# can_unisolated_lemo.net
KiCad netlist of a schematic drawn in Altium Designer
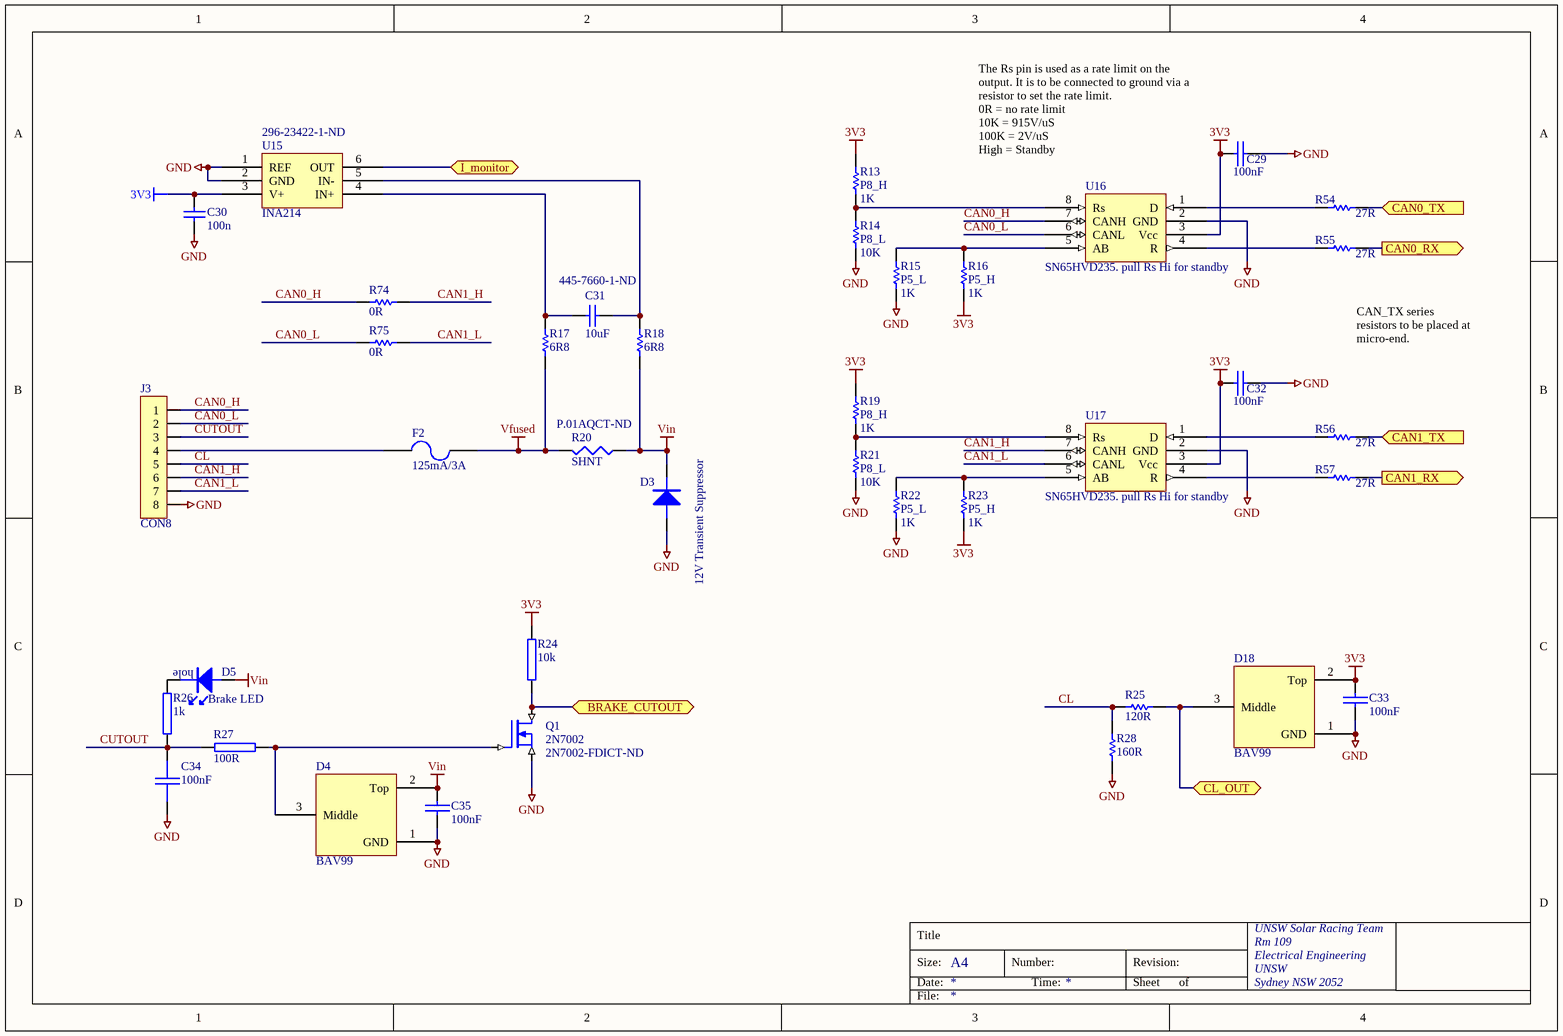
[diagram p0: can_unisolated_lemo.SchDoc]

(export (version "E")
  (design (tool "Eeschema 10.0.6"))
  (components
    (comp (ref "C29")
      (value "100nF")
      (footprint "0603")
      (description "Capacitor")
      (libsource (lib "*") (part "CAP"))
    )
    (comp (ref "C30")
      (value "100n")
      (footprint "0603")
      (description "Capacitor (Semiconductor SIM Model)")
      (fields (field (name "PUBLISHER") "Altium Limited"))
      (libsource (lib "Miscellaneous Devices") (part "Cap Semi"))
    )
    (comp (ref "C31")
      (value "10uF")
      (footprint "0805")
      (description "Capacitor (Semiconductor SIM Model)")
      (fields
        (field (name "SUPPLIER PART NUMBER 1") "445-7660-1-ND")
        (field (name "MANUFACTURER") "TDK Corporation")
        (field (name "MANUFACTURER PART NUMBER") "C2012X5R1A106K125AB")
      )
      (libsource (lib "Miscellaneous Devices") (part "Cap Semi"))
    )
    (comp (ref "C32")
      (value "100nF")
      (footprint "0603")
      (description "Capacitor")
      (libsource (lib "*") (part "CAP"))
    )
    (comp (ref "C33")
      (value "100nF")
      (footprint "0603")
      (description "Capacitor")
      (libsource (lib "*") (part "CAP"))
    )
    (comp (ref "C34")
      (value "100nF")
      (footprint "0603")
      (description "Capacitor")
      (libsource (lib "Miscellaneous Devices") (part "CAP"))
    )
    (comp (ref "C35")
      (value "100nF")
      (footprint "0603")
      (description "Capacitor")
      (libsource (lib "*") (part "CAP"))
    )
    (comp (ref "D3")
      (value "12V Transient Suppressor")
      (footprint "SMA")
      (description "Diode")
      (libsource (lib "RCLDQ") (part "DIODE"))
    )
    (comp (ref "D4")
      (value "BAV99")
      (footprint "SOT23-3")
      (description "Dual Diode")
      (libsource (lib "Miscellaneous") (part "BAV99"))
    )
    (comp (ref "D5")
      (value "Brake LED")
      (footprint "LED0.1")
      (description "through hole LED")
      (libsource (lib "RCLDQ") (part "LED_HOLE"))
    )
    (comp (ref "D18")
      (value "BAV99")
      (footprint "SOT23-3")
      (description "Dual Diode")
      (libsource (lib "Miscellaneous") (part "BAV99"))
    )
    (comp (ref "F2")
      (value "125mA/3A")
      (footprint "LITTELFUSE-154")
      (description "Fuse")
      (libsource (lib "*") (part "FUSE2"))
    )
    (comp (ref "J3")
      (value "CON8")
      (footprint "LEMO_1B_308")
      (description "Connector")
      (libsource (lib "steve") (part "CON8"))
    )
    (comp (ref "Q1")
      (value "2N7002")
      (footprint "SOT23-3")
      (description "MOSFET N-CH 60V 115MA SOT23-3")
      (fields
        (field (name "SUPPLIER PART NUMBER 1") "2N7002-FDICT-ND")
        (field (name "MANUFACTURER") "Diodes Inc")
        (field (name "MANUFACTURER PART NUMBER") "2N7002-7-F")
      )
      (libsource (lib "*") (part "N-MOSFET"))
    )
    (comp (ref "R13")
      (value "P8_H")
      (footprint "0603")
      (description "Semiconductor Resistor")
      (fields (field (name "ALTIUM_VALUE") "1K") (field (name "PUBLISHER") "Altium Limited"))
      (libsource (lib "Miscellaneous Devices") (part "Res Semi"))
    )
    (comp (ref "R14")
      (value "P8_L")
      (footprint "0603")
      (description "Semiconductor Resistor")
      (fields (field (name "ALTIUM_VALUE") "10K") (field (name "PUBLISHER") "Altium Limited"))
      (libsource (lib "Miscellaneous Devices") (part "Res Semi"))
    )
    (comp (ref "R15")
      (value "P5_L")
      (footprint "0603")
      (description "Semiconductor Resistor")
      (fields (field (name "ALTIUM_VALUE") "1K") (field (name "PUBLISHER") "Altium Limited"))
      (libsource (lib "Miscellaneous Devices") (part "Res Semi"))
    )
    (comp (ref "R16")
      (value "P5_H")
      (footprint "0603")
      (description "Semiconductor Resistor")
      (fields (field (name "ALTIUM_VALUE") "1K") (field (name "PUBLISHER") "Altium Limited"))
      (libsource (lib "Miscellaneous Devices") (part "Res Semi"))
    )
    (comp (ref "R17")
      (value "6R8")
      (footprint "0603")
      (description "Semiconductor Resistor")
      (fields
        (field (name "MANUFACTURER") "Panasonic Electronic Components")
        (field (name "MANUFACTURER PART NUMBER") "ERJ-3GEYJ6R8V")
        (field (name "PUBLISHER") "Altium Limited")
      )
      (libsource (lib "Miscellaneous Devices") (part "Res Semi"))
    )
    (comp (ref "R18")
      (value "6R8")
      (footprint "0603")
      (description "Semiconductor Resistor")
      (fields
        (field (name "MANUFACTURER") "Panasonic Electronic Components")
        (field (name "MANUFACTURER PART NUMBER") "ERJ-3GEYJ6R8V")
        (field (name "PUBLISHER") "Altium Limited")
      )
      (libsource (lib "Miscellaneous Devices") (part "Res Semi"))
    )
    (comp (ref "R19")
      (value "P8_H")
      (footprint "0603")
      (description "Semiconductor Resistor")
      (fields (field (name "ALTIUM_VALUE") "1K") (field (name "PUBLISHER") "Altium Limited"))
      (libsource (lib "Miscellaneous Devices") (part "Res Semi"))
    )
    (comp (ref "R20")
      (value "SHNT")
      (footprint "0805")
      (description "Resistor")
      (fields
        (field (name "SUPPLIER PART NUMBER 1") "P.01AQCT-ND")
        (field (name "MANUFACTURER") "Panasonic Electronic Components")
        (field (name "MANUFACTURER PART NUMBER") "ERJ-6BWFR010V")
        (field (name "PUBLISHER") "Altium Limited")
      )
      (libsource (lib "Miscellaneous Devices") (part "Res3"))
    )
    (comp (ref "R21")
      (value "P8_L")
      (footprint "0603")
      (description "Semiconductor Resistor")
      (fields (field (name "ALTIUM_VALUE") "10K") (field (name "PUBLISHER") "Altium Limited"))
      (libsource (lib "Miscellaneous Devices") (part "Res Semi"))
    )
    (comp (ref "R22")
      (value "P5_L")
      (footprint "0603")
      (description "Semiconductor Resistor")
      (fields (field (name "ALTIUM_VALUE") "1K") (field (name "PUBLISHER") "Altium Limited"))
      (libsource (lib "Miscellaneous Devices") (part "Res Semi"))
    )
    (comp (ref "R23")
      (value "P5_H")
      (footprint "0603")
      (description "Semiconductor Resistor")
      (fields (field (name "ALTIUM_VALUE") "1K") (field (name "PUBLISHER") "Altium Limited"))
      (libsource (lib "Miscellaneous Devices") (part "Res Semi"))
    )
    (comp (ref "R24")
      (value "10k")
      (footprint "0603")
      (description "Standard Resistor")
      (libsource (lib "*") (part "RES"))
    )
    (comp (ref "R25")
      (value "120R")
      (footprint "0603")
      (description "Semiconductor Resistor")
      (fields
        (field (name "MANUFACTURER") "Panasonic Electronic Components")
        (field (name "MANUFACTURER PART NUMBER") "ERJ-3EKF1200V")
        (field (name "PUBLISHER") "Altium Limited")
      )
      (libsource (lib "Miscellaneous Devices") (part "Res Semi"))
    )
    (comp (ref "R26")
      (value "1k")
      (footprint "0603")
      (description "Standard Resistor")
      (libsource (lib "*") (part "RES"))
    )
    (comp (ref "R27")
      (value "100R")
      (footprint "0603")
      (description "Standard Resistor")
      (libsource (lib "*") (part "RES"))
    )
    (comp (ref "R28")
      (value "160R")
      (footprint "0603")
      (description "Semiconductor Resistor")
      (fields
        (field (name "MANUFACTURER") "Panasonic Electronic Components")
        (field (name "MANUFACTURER PART NUMBER") "ERJ-2RKF1600X")
        (field (name "PUBLISHER") "Altium Limited")
      )
      (libsource (lib "Miscellaneous Devices") (part "Res Semi"))
    )
    (comp (ref "R54")
      (value "27R")
      (footprint "0603")
      (description "Semiconductor Resistor")
      (fields
        (field (name "MANUFACTURER") "Panasonic Electronic Components")
        (field (name "MANUFACTURER PART NUMBER") "ERJ-3EKF27R0V")
        (field (name "PUBLISHER") "Altium Limited")
      )
      (libsource (lib "Miscellaneous Devices") (part "Res Semi"))
    )
    (comp (ref "R55")
      (value "27R")
      (footprint "0603")
      (description "Semiconductor Resistor")
      (fields
        (field (name "MANUFACTURER") "Panasonic Electronic Components")
        (field (name "MANUFACTURER PART NUMBER") "ERJ-3EKF27R0V")
        (field (name "PUBLISHER") "Altium Limited")
      )
      (libsource (lib "Miscellaneous Devices") (part "Res Semi"))
    )
    (comp (ref "R56")
      (value "27R")
      (footprint "0603")
      (description "Semiconductor Resistor")
      (fields
        (field (name "MANUFACTURER") "Panasonic Electronic Components")
        (field (name "MANUFACTURER PART NUMBER") "ERJ-3EKF27R0V")
        (field (name "PUBLISHER") "Altium Limited")
      )
      (libsource (lib "Miscellaneous Devices") (part "Res Semi"))
    )
    (comp (ref "R57")
      (value "27R")
      (footprint "0603")
      (description "Semiconductor Resistor")
      (fields
        (field (name "MANUFACTURER") "Panasonic Electronic Components")
        (field (name "MANUFACTURER PART NUMBER") "ERJ-3EKF27R0V")
        (field (name "PUBLISHER") "Altium Limited")
      )
      (libsource (lib "Miscellaneous Devices") (part "Res Semi"))
    )
    (comp (ref "R74")
      (value "0R")
      (footprint "0603")
      (description "Semiconductor Resistor")
      (fields (field (name "PUBLISHER") "Altium Limited"))
      (libsource (lib "Miscellaneous Devices") (part "Res Semi"))
    )
    (comp (ref "R75")
      (value "0R")
      (footprint "0603")
      (description "Semiconductor Resistor")
      (fields (field (name "PUBLISHER") "Altium Limited"))
      (libsource (lib "Miscellaneous Devices") (part "Res Semi"))
    )
    (comp (ref "U15")
      (value "INA214")
      (footprint "SC70-6")
      (description "Current Shunt Monitor")
      (fields
        (field (name "SUPPLIER PART NUMBER 1") "296-23422-1-ND")
        (field (name "MANUFACTURER") "Texas Instruments")
        (field (name "MANUFACTURER PART NUMBER") "INA214AIDCKT")
      )
      (libsource (lib "MiscellaneousIC") (part "ina214"))
    )
    (comp (ref "U16")
      (value "SN65HVD235. pull Rs Hi for standby")
      (footprint "SO8")
      (description "3.3V CAN XCVR W/STANDBY")
      (libsource (lib "CAN") (part "SN65HVD235"))
    )
    (comp (ref "U17")
      (value "SN65HVD235. pull Rs Hi for standby")
      (footprint "SO8")
      (description "3.3V CAN XCVR W/STANDBY")
      (libsource (lib "CAN") (part "SN65HVD235"))
    )
  )
  (nets
    (net (code "1") (name "/BRAKE_CUTOUT") (class "Default")
      (node (ref "Q1") (pin "D") (pinfunction "D_D") (pintype "input"))
      (node (ref "R24") (pin "1") (pintype "passive"))
    )
    (net (code "2") (name "/CAN0_H") (class "Default")
      (node (ref "J3") (pin "1") (pinfunction "1_1") (pintype "passive"))
      (node (ref "R74") (pin "1") (pinfunction "1_1") (pintype "passive"))
      (node (ref "U16") (pin "7") (pinfunction "CANH_7") (pintype "bidirectional"))
    )
    (net (code "3") (name "/CAN0_L") (class "Default")
      (node (ref "J3") (pin "2") (pinfunction "2_2") (pintype "passive"))
      (node (ref "R75") (pin "1") (pinfunction "1_1") (pintype "passive"))
      (node (ref "U16") (pin "6") (pinfunction "CANL_6") (pintype "bidirectional"))
    )
    (net (code "4") (name "/CAN0_RX") (class "Default")
      (node (ref "R55") (pin "1") (pinfunction "1_1") (pintype "passive"))
    )
    (net (code "5") (name "/CAN0_TX") (class "Default")
      (node (ref "R54") (pin "1") (pinfunction "1_1") (pintype "passive"))
    )
    (net (code "6") (name "/CAN1_H") (class "Default")
      (node (ref "J3") (pin "6") (pinfunction "6_6") (pintype "passive"))
      (node (ref "R74") (pin "2") (pinfunction "2_2") (pintype "passive"))
      (node (ref "U17") (pin "7") (pinfunction "CANH_7") (pintype "bidirectional"))
    )
    (net (code "7") (name "/CAN1_L") (class "Default")
      (node (ref "J3") (pin "7") (pinfunction "7_7") (pintype "passive"))
      (node (ref "R75") (pin "2") (pinfunction "2_2") (pintype "passive"))
      (node (ref "U17") (pin "6") (pinfunction "CANL_6") (pintype "bidirectional"))
    )
    (net (code "8") (name "/CAN1_RX") (class "Default")
      (node (ref "R57") (pin "1") (pinfunction "1_1") (pintype "passive"))
    )
    (net (code "9") (name "/CAN1_TX") (class "Default")
      (node (ref "R56") (pin "1") (pinfunction "1_1") (pintype "passive"))
    )
    (net (code "10") (name "/CL") (class "Default")
      (node (ref "J3") (pin "5") (pinfunction "5_5") (pintype "passive"))
      (node (ref "R25") (pin "2") (pinfunction "2_2") (pintype "passive"))
      (node (ref "R28") (pin "2") (pinfunction "2_2") (pintype "passive"))
    )
    (net (code "11") (name "/CL_OUT") (class "Default")
      (node (ref "D18") (pin "3") (pinfunction "Middle_3") (pintype "passive"))
      (node (ref "R25") (pin "1") (pinfunction "1_1") (pintype "passive"))
    )
    (net (code "12") (name "/CUTOUT") (class "Default")
      (node (ref "C34") (pin "1") (pinfunction "1_1") (pintype "passive"))
      (node (ref "J3") (pin "3") (pinfunction "3_3") (pintype "passive"))
      (node (ref "R26") (pin "2") (pintype "passive"))
      (node (ref "R27") (pin "1") (pintype "passive"))
    )
    (net (code "13") (name "/I_monitor") (class "Default")
      (node (ref "U15") (pin "6") (pinfunction "OUT_6") (pintype "power_in"))
    )
    (net (code "14") (name "3V3") (class "Default")
      (node (ref "C29") (pin "2") (pinfunction "2_2") (pintype "passive"))
      (node (ref "C30") (pin "2") (pinfunction "2_2") (pintype "passive"))
      (node (ref "C32") (pin "2") (pinfunction "2_2") (pintype "passive"))
      (node (ref "C33") (pin "1") (pinfunction "1_1") (pintype "passive"))
      (node (ref "D18") (pin "2") (pinfunction "Top_2") (pintype "passive"))
      (node (ref "R13") (pin "2") (pinfunction "2_2") (pintype "passive"))
      (node (ref "R16") (pin "1") (pinfunction "1_1") (pintype "passive"))
      (node (ref "R19") (pin "2") (pinfunction "2_2") (pintype "passive"))
      (node (ref "R23") (pin "1") (pinfunction "1_1") (pintype "passive"))
      (node (ref "R24") (pin "2") (pintype "passive"))
      (node (ref "U15") (pin "3") (pinfunction "V+_3") (pintype "power_in"))
      (node (ref "U16") (pin "3") (pinfunction "Vcc_3") (pintype "power_in"))
      (node (ref "U17") (pin "3") (pinfunction "Vcc_3") (pintype "power_in"))
    )
    (net (code "15") (name "GND") (class "Default")
      (node (ref "C29") (pin "1") (pinfunction "1_1") (pintype "passive"))
      (node (ref "C30") (pin "1") (pinfunction "1_1") (pintype "passive"))
      (node (ref "C32") (pin "1") (pinfunction "1_1") (pintype "passive"))
      (node (ref "C33") (pin "2") (pinfunction "2_2") (pintype "passive"))
      (node (ref "C34") (pin "2") (pinfunction "2_2") (pintype "passive"))
      (node (ref "C35") (pin "2") (pinfunction "2_2") (pintype "passive"))
      (node (ref "D18") (pin "1") (pinfunction "GND_1") (pintype "passive"))
      (node (ref "D3") (pin "A") (pinfunction "A_A") (pintype "passive"))
      (node (ref "D4") (pin "1") (pinfunction "GND_1") (pintype "passive"))
      (node (ref "J3") (pin "8") (pinfunction "8_8") (pintype "passive"))
      (node (ref "Q1") (pin "S") (pinfunction "S_S") (pintype "input"))
      (node (ref "R14") (pin "1") (pinfunction "1_1") (pintype "passive"))
      (node (ref "R15") (pin "1") (pinfunction "1_1") (pintype "passive"))
      (node (ref "R21") (pin "1") (pinfunction "1_1") (pintype "passive"))
      (node (ref "R22") (pin "1") (pinfunction "1_1") (pintype "passive"))
      (node (ref "R28") (pin "1") (pinfunction "1_1") (pintype "passive"))
      (node (ref "U15") (pin "1") (pinfunction "REF_1") (pintype "power_in"))
      (node (ref "U15") (pin "2") (pinfunction "GND_2") (pintype "power_in"))
      (node (ref "U16") (pin "2") (pinfunction "GND_2") (pintype "power_in"))
      (node (ref "U17") (pin "2") (pinfunction "GND_2") (pintype "power_in"))
    )
    (net (code "16") (name "Net-(D4-Middle)") (class "Default")
      (node (ref "D4") (pin "3") (pinfunction "Middle_3") (pintype "passive"))
      (node (ref "Q1") (pin "G") (pinfunction "G_G") (pintype "input"))
      (node (ref "R27") (pin "2") (pintype "passive"))
    )
    (net (code "17") (name "Net-(D5-PadK)") (class "Default")
      (node (ref "D5") (pin "K") (pinfunction "K_K") (pintype "passive"))
      (node (ref "R26") (pin "1") (pintype "passive"))
    )
    (net (code "18") (name "Net-(F2-Pad1)") (class "Default")
      (node (ref "F2") (pin "1") (pinfunction "1_1") (pintype "passive"))
      (node (ref "J3") (pin "4") (pinfunction "4_4") (pintype "passive"))
    )
    (net (code "19") (name "Net-(U15-IN+)") (class "Default")
      (node (ref "C31") (pin "1") (pinfunction "1_1") (pintype "passive"))
      (node (ref "R17") (pin "1") (pinfunction "1_1") (pintype "passive"))
      (node (ref "U15") (pin "4") (pinfunction "IN+_4") (pintype "power_in"))
    )
    (net (code "20") (name "Net-(U15-IN-)") (class "Default")
      (node (ref "C31") (pin "2") (pinfunction "2_2") (pintype "passive"))
      (node (ref "R18") (pin "1") (pinfunction "1_1") (pintype "passive"))
      (node (ref "U15") (pin "5") (pinfunction "IN-_5") (pintype "power_in"))
    )
    (net (code "21") (name "Net-(U16-AB)") (class "Default")
      (node (ref "R15") (pin "2") (pinfunction "2_2") (pintype "passive"))
      (node (ref "R16") (pin "2") (pinfunction "2_2") (pintype "passive"))
      (node (ref "U16") (pin "5") (pinfunction "AB_5") (pintype "input"))
    )
    (net (code "22") (name "Net-(U16-D)") (class "Default")
      (node (ref "R54") (pin "2") (pinfunction "2_2") (pintype "passive"))
      (node (ref "U16") (pin "1") (pinfunction "D_1") (pintype "input"))
    )
    (net (code "23") (name "Net-(U16-R)") (class "Default")
      (node (ref "R55") (pin "2") (pinfunction "2_2") (pintype "passive"))
      (node (ref "U16") (pin "4") (pinfunction "R_4") (pintype "output"))
    )
    (net (code "24") (name "Net-(U16-Rs)") (class "Default")
      (node (ref "R13") (pin "1") (pinfunction "1_1") (pintype "passive"))
      (node (ref "R14") (pin "2") (pinfunction "2_2") (pintype "passive"))
      (node (ref "U16") (pin "8") (pinfunction "Rs_8") (pintype "input"))
    )
    (net (code "25") (name "Net-(U17-AB)") (class "Default")
      (node (ref "R22") (pin "2") (pinfunction "2_2") (pintype "passive"))
      (node (ref "R23") (pin "2") (pinfunction "2_2") (pintype "passive"))
      (node (ref "U17") (pin "5") (pinfunction "AB_5") (pintype "input"))
    )
    (net (code "26") (name "Net-(U17-D)") (class "Default")
      (node (ref "R56") (pin "2") (pinfunction "2_2") (pintype "passive"))
      (node (ref "U17") (pin "1") (pinfunction "D_1") (pintype "input"))
    )
    (net (code "27") (name "Net-(U17-R)") (class "Default")
      (node (ref "R57") (pin "2") (pinfunction "2_2") (pintype "passive"))
      (node (ref "U17") (pin "4") (pinfunction "R_4") (pintype "output"))
    )
    (net (code "28") (name "Net-(U17-Rs)") (class "Default")
      (node (ref "R19") (pin "1") (pinfunction "1_1") (pintype "passive"))
      (node (ref "R21") (pin "2") (pinfunction "2_2") (pintype "passive"))
      (node (ref "U17") (pin "8") (pinfunction "Rs_8") (pintype "input"))
    )
    (net (code "29") (name "Vfused") (class "Default")
      (node (ref "F2") (pin "2") (pinfunction "2_2") (pintype "passive"))
      (node (ref "R17") (pin "2") (pinfunction "2_2") (pintype "passive"))
      (node (ref "R20") (pin "2") (pinfunction "2_2") (pintype "passive"))
    )
    (net (code "30") (name "Vin") (class "Default")
      (node (ref "C35") (pin "1") (pinfunction "1_1") (pintype "passive"))
      (node (ref "D3") (pin "K") (pinfunction "K_K") (pintype "passive"))
      (node (ref "D4") (pin "2") (pinfunction "Top_2") (pintype "passive"))
      (node (ref "D5") (pin "A") (pinfunction "A_A") (pintype "passive"))
      (node (ref "R18") (pin "2") (pinfunction "2_2") (pintype "passive"))
      (node (ref "R20") (pin "1") (pinfunction "1_1") (pintype "passive"))
    )
  )
)
